# Tarjeta1.net
KiCad netlist of a schematic drawn in EAGLE
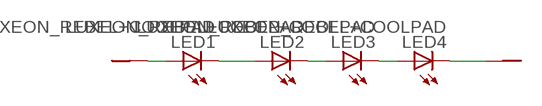
[diagram p0: schematic, sheet 1]

(export (version "E")
  (design (tool "Eeschema 10.0.6"))
  (components
    (comp (ref "LED1")
      (value "LUXEON_REBEL+COOLPAD")
      (footprint "eagle-import:LUXEON_REBEL+COOLPAD")
      (libsource (lib "eagle-import") (part "LUXEON_REBEL+COOLPAD"))
    )
    (comp (ref "LED2")
      (value "LUXEON_REBEL+COOLPAD")
      (footprint "eagle-import:LUXEON_REBEL+COOLPAD")
      (libsource (lib "eagle-import") (part "LUXEON_REBEL+COOLPAD"))
    )
    (comp (ref "LED3")
      (value "LUXEON_REBEL+COOLPAD")
      (footprint "eagle-import:LUXEON_REBEL+COOLPAD")
      (libsource (lib "eagle-import") (part "LUXEON_REBEL+COOLPAD"))
    )
    (comp (ref "LED4")
      (value "LUXEON_REBEL+COOLPAD")
      (footprint "eagle-import:LUXEON_REBEL+COOLPAD")
      (libsource (lib "eagle-import") (part "LUXEON_REBEL+COOLPAD"))
    )
    (comp (ref "U$1")
      (value "POWER_PIN")
      (footprint "eagle-import:POWER_PIN")
      (libsource (lib "eagle-import") (part "POWER_PIN"))
    )
    (comp (ref "U$2")
      (value "POWER_PIN")
      (footprint "eagle-import:POWER_PIN")
      (libsource (lib "eagle-import") (part "POWER_PIN"))
    )
  )
  (nets
    (net (code "1") (name "Net-(LED1-PadA)") (class "Default")
      (node (ref "LED1") (pin "A") (pinfunction "A_A") (pintype "passive"))
      (node (ref "LED1") (pin "A@1") (pinfunction "A_A@1") (pintype "passive"))
      (node (ref "U$1") (pin "P$1") (pinfunction "P$1_P$1") (pintype "bidirectional"))
    )
    (net (code "2") (name "Net-(LED1-PadC)") (class "Default")
      (node (ref "LED1") (pin "C") (pinfunction "C_C") (pintype "passive"))
      (node (ref "LED1") (pin "C@1") (pinfunction "C_C@1") (pintype "passive"))
      (node (ref "LED2") (pin "A") (pinfunction "A_A") (pintype "passive"))
      (node (ref "LED2") (pin "A@1") (pinfunction "A_A@1") (pintype "passive"))
    )
    (net (code "3") (name "Net-(LED2-PadC)") (class "Default")
      (node (ref "LED2") (pin "C") (pinfunction "C_C") (pintype "passive"))
      (node (ref "LED2") (pin "C@1") (pinfunction "C_C@1") (pintype "passive"))
      (node (ref "LED3") (pin "A") (pinfunction "A_A") (pintype "passive"))
      (node (ref "LED3") (pin "A@1") (pinfunction "A_A@1") (pintype "passive"))
    )
    (net (code "4") (name "Net-(LED3-PadC)") (class "Default")
      (node (ref "LED3") (pin "C") (pinfunction "C_C") (pintype "passive"))
      (node (ref "LED3") (pin "C@1") (pinfunction "C_C@1") (pintype "passive"))
      (node (ref "LED4") (pin "A") (pinfunction "A_A") (pintype "passive"))
      (node (ref "LED4") (pin "A@1") (pinfunction "A_A@1") (pintype "passive"))
    )
    (net (code "5") (name "Net-(LED4-PadC)") (class "Default")
      (node (ref "LED4") (pin "C") (pinfunction "C_C") (pintype "passive"))
      (node (ref "LED4") (pin "C@1") (pinfunction "C_C@1") (pintype "passive"))
      (node (ref "U$2") (pin "P$1") (pinfunction "P$1_P$1") (pintype "bidirectional"))
    )
  )
)
